# Bottom.net
KiCad netlist of a schematic drawn in EAGLE
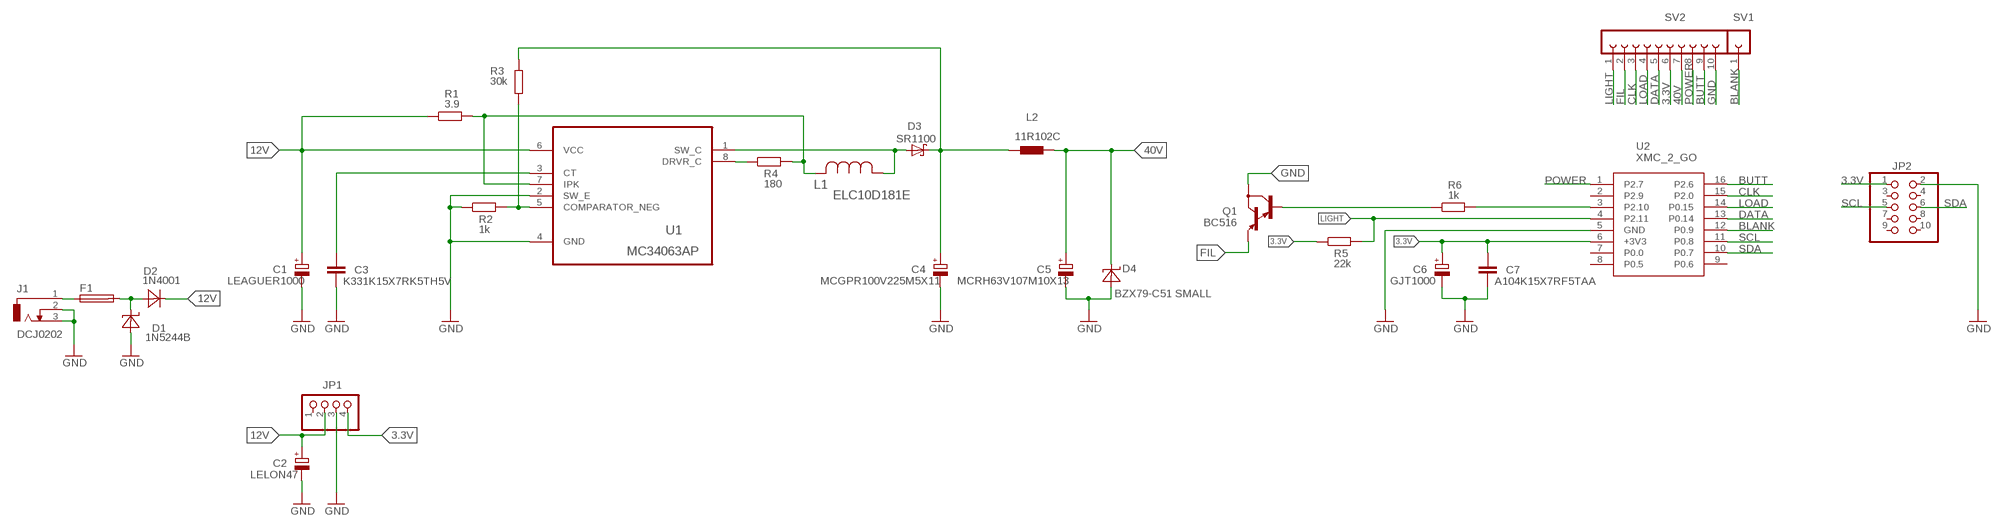
[diagram p0: schematic, sheet 1]

(export (version "E")
  (design (tool "Eeschema 10.0.6"))
  (components
    (comp (ref "C1")
      (value "LEAGUER1000")
      (footprint "eagle-import:E5-10")
      (libsource (lib "eagle-import") (part "LEAGUER1000"))
    )
    (comp (ref "C2")
      (value "LELON47")
      (footprint "eagle-import:E2,5-6")
      (libsource (lib "eagle-import") (part "LELON47"))
    )
    (comp (ref "C3")
      (value "K331K15X7RK5TH5V")
      (footprint "eagle-import:C025-025X050")
      (libsource (lib "eagle-import") (part "K331K15X7RK5TH5V"))
    )
    (comp (ref "C4")
      (value "MCGPR100V225M5X11")
      (footprint "eagle-import:E2,5-5")
      (libsource (lib "eagle-import") (part "MCGPR100V225M5X11"))
    )
    (comp (ref "C5")
      (value "MCRH63V107M10X13")
      (footprint "eagle-import:E5-10")
      (libsource (lib "eagle-import") (part "MCRH63V107M10X13"))
    )
    (comp (ref "C6")
      (value "GJT1000")
      (footprint "eagle-import:E2,5-8")
      (libsource (lib "eagle-import") (part "GJT1000"))
    )
    (comp (ref "C7")
      (value "A104K15X7RF5TAA")
      (footprint "eagle-import:C025-025X050")
      (libsource (lib "eagle-import") (part "A104K15X7RF5TAA"))
    )
    (comp (ref "D1")
      (value "1N5244B")
      (footprint "eagle-import:DO41-7")
      (libsource (lib "eagle-import") (part "1N5244B"))
    )
    (comp (ref "D2")
      (value "1N4001")
      (footprint "eagle-import:DO41-7")
      (libsource (lib "eagle-import") (part "1N4001"))
    )
    (comp (ref "D3")
      (value "SR1100")
      (footprint "eagle-import:DO41-7")
      (libsource (lib "eagle-import") (part "SR1100"))
    )
    (comp (ref "D4")
      (value "BZX79-C51 SMALL")
      (footprint "eagle-import:DO35-7")
      (libsource (lib "eagle-import") (part "BZX79-C51"))
    )
    (comp (ref "F1")
      (value "SH22,5")
      (footprint "eagle-import:SH22,5")
      (fields (field (name "MF") "SCHURTER") (field (name "MPN") "0031.8201"))
      (libsource (lib "eagle-import") (part "SH22,5"))
    )
    (comp (ref "J1")
      (value "DCJ0202")
      (footprint "eagle-import:DCJ0202")
      (libsource (lib "eagle-import") (part "DCJ0202"))
    )
    (comp (ref "JP1")
      (value "PINHD-1X4")
      (footprint "eagle-import:1X04")
      (libsource (lib "eagle-import") (part "PINHD-1X4"))
    )
    (comp (ref "JP2")
      (value "PINHD-2X5/90")
      (footprint "eagle-import:2X05_90")
      (libsource (lib "eagle-import") (part "PINHD-2X5/90"))
    )
    (comp (ref "L1")
      (value "ELC10D181E")
      (footprint "eagle-import:IND_ELC10D")
      (libsource (lib "eagle-import") (part "ELC-10D10D181E"))
    )
    (comp (ref "L2")
      (value "11R102C")
      (footprint "eagle-import:L2,5-5")
      (libsource (lib "eagle-import") (part "11R102C"))
    )
    (comp (ref "Q1")
      (value "BC516")
      (footprint "eagle-import:TO92")
      (libsource (lib "eagle-import") (part "BC516"))
    )
    (comp (ref "R1")
      (value "3.9")
      (footprint "eagle-import:0207_10")
      (libsource (lib "eagle-import") (part "R-EU_0207/10"))
    )
    (comp (ref "R2")
      (value "1k")
      (footprint "eagle-import:0207_10")
      (libsource (lib "eagle-import") (part "R-EU_0207/10"))
    )
    (comp (ref "R3")
      (value "30k")
      (footprint "eagle-import:0207_10")
      (libsource (lib "eagle-import") (part "R-EU_0207/10"))
    )
    (comp (ref "R4")
      (value "180")
      (footprint "eagle-import:0207_10")
      (libsource (lib "eagle-import") (part "R-EU_0207/10"))
    )
    (comp (ref "R5")
      (value "22k")
      (footprint "eagle-import:0207_10")
      (libsource (lib "eagle-import") (part "R-EU_0207/10"))
    )
    (comp (ref "R6")
      (value "1k")
      (footprint "eagle-import:0207_10")
      (libsource (lib "eagle-import") (part "R-EU_0207/10"))
    )
    (comp (ref "SV1")
      (value "FE01")
      (footprint "eagle-import:FE05-1")
      (libsource (lib "eagle-import") (part "FE01"))
    )
    (comp (ref "SV2")
      (value "FE10-1")
      (footprint "eagle-import:FE10")
      (libsource (lib "eagle-import") (part "FE10-1"))
    )
    (comp (ref "U1")
      (value "MC34063AP")
      (footprint "eagle-import:DIP254P762X508-8")
      (libsource (lib "eagle-import") (part "MC34063AP"))
    )
    (comp (ref "U2")
      (value "XMC_2_GO")
      (footprint "eagle-import:XMC_2_GO")
      (libsource (lib "eagle-import") (part "XMC_2_GO"))
    )
  )
  (nets
    (net (code "1") (name "/BLANK") (class "Default")
      (node (ref "SV1") (pin "1") (pinfunction "5_1") (pintype "passive"))
      (node (ref "U2") (pin "12") (pinfunction "P0.9_12") (pintype "bidirectional"))
    )
    (net (code "2") (name "/BUTT") (class "Default")
      (node (ref "SV2") (pin "9") (pinfunction "9_9") (pintype "passive"))
      (node (ref "U2") (pin "16") (pinfunction "P2.6_16") (pintype "bidirectional"))
    )
    (net (code "3") (name "/CLK") (class "Default")
      (node (ref "SV2") (pin "3") (pinfunction "3_3") (pintype "passive"))
      (node (ref "U2") (pin "15") (pinfunction "P2.0_15") (pintype "bidirectional"))
    )
    (net (code "4") (name "/DATA") (class "Default")
      (node (ref "SV2") (pin "5") (pinfunction "5_5") (pintype "passive"))
      (node (ref "U2") (pin "13") (pinfunction "P0.14_13") (pintype "bidirectional"))
    )
    (net (code "5") (name "/LOAD") (class "Default")
      (node (ref "SV2") (pin "4") (pinfunction "4_4") (pintype "passive"))
      (node (ref "U2") (pin "14") (pinfunction "P0.15_14") (pintype "bidirectional"))
    )
    (net (code "6") (name "/POWER") (class "Default")
      (node (ref "SV2") (pin "8") (pinfunction "8_8") (pintype "passive"))
      (node (ref "U2") (pin "1") (pinfunction "P2.7_1") (pintype "bidirectional"))
    )
    (net (code "7") (name "/SCL") (class "Default")
      (node (ref "JP2") (pin "5") (pinfunction "5_5") (pintype "passive"))
      (node (ref "U2") (pin "11") (pinfunction "P0.8_11") (pintype "bidirectional"))
    )
    (net (code "8") (name "/SDA") (class "Default")
      (node (ref "JP2") (pin "6") (pinfunction "6_6") (pintype "passive"))
      (node (ref "U2") (pin "10") (pinfunction "P0.7_10") (pintype "bidirectional"))
    )
    (net (code "9") (name "3.3V") (class "Default")
      (node (ref "C6") (pin "+") (pinfunction "+_+") (pintype "passive"))
      (node (ref "C7") (pin "1") (pinfunction "1_1") (pintype "passive"))
      (node (ref "JP1") (pin "4") (pinfunction "4_4") (pintype "passive"))
      (node (ref "JP2") (pin "1") (pinfunction "1_1") (pintype "passive"))
      (node (ref "R5") (pin "1") (pinfunction "1_1") (pintype "passive"))
      (node (ref "SV2") (pin "6") (pinfunction "6_6") (pintype "passive"))
      (node (ref "U2") (pin "6") (pinfunction "+3V3_6") (pintype "bidirectional"))
    )
    (net (code "10") (name "12V") (class "Default")
      (node (ref "C1") (pin "+") (pinfunction "+_+") (pintype "passive"))
      (node (ref "C2") (pin "+") (pinfunction "+_+") (pintype "passive"))
      (node (ref "D2") (pin "C") (pinfunction "C_C") (pintype "passive"))
      (node (ref "JP1") (pin "2") (pinfunction "2_2") (pintype "passive"))
      (node (ref "R1") (pin "1") (pinfunction "1_1") (pintype "passive"))
      (node (ref "U1") (pin "6") (pinfunction "VCC_6") (pintype "power_in"))
    )
    (net (code "11") (name "40V") (class "Default")
      (node (ref "C5") (pin "+") (pinfunction "+_+") (pintype "passive"))
      (node (ref "D4") (pin "C") (pinfunction "C_C") (pintype "passive"))
      (node (ref "L2") (pin "2") (pinfunction "2_2") (pintype "passive"))
      (node (ref "SV2") (pin "7") (pinfunction "7_7") (pintype "passive"))
    )
    (net (code "12") (name "FIL") (class "Default")
      (node (ref "Q1") (pin "1") (pinfunction "E_1") (pintype "passive"))
      (node (ref "SV2") (pin "2") (pinfunction "2_2") (pintype "passive"))
    )
    (net (code "13") (name "GND") (class "Default")
      (node (ref "C1") (pin "-") (pinfunction "-_-") (pintype "passive"))
      (node (ref "C2") (pin "-") (pinfunction "-_-") (pintype "passive"))
      (node (ref "C3") (pin "2") (pinfunction "2_2") (pintype "passive"))
      (node (ref "C4") (pin "-") (pinfunction "-_-") (pintype "passive"))
      (node (ref "C5") (pin "-") (pinfunction "-_-") (pintype "passive"))
      (node (ref "C6") (pin "-") (pinfunction "-_-") (pintype "passive"))
      (node (ref "C7") (pin "2") (pinfunction "2_2") (pintype "passive"))
      (node (ref "D1") (pin "A") (pinfunction "A_A") (pintype "passive"))
      (node (ref "D4") (pin "A") (pinfunction "A_A") (pintype "passive"))
      (node (ref "J1") (pin "2") (pinfunction "2_2") (pintype "passive"))
      (node (ref "J1") (pin "3") (pinfunction "3_3") (pintype "passive"))
      (node (ref "JP1") (pin "3") (pinfunction "3_3") (pintype "passive"))
      (node (ref "JP2") (pin "2") (pinfunction "2_2") (pintype "passive"))
      (node (ref "Q1") (pin "3") (pinfunction "C_3") (pintype "passive"))
      (node (ref "R2") (pin "1") (pinfunction "1_1") (pintype "passive"))
      (node (ref "SV2") (pin "10") (pinfunction "10_10") (pintype "passive"))
      (node (ref "U1") (pin "2") (pinfunction "SW_E_2") (pintype "input"))
      (node (ref "U1") (pin "4") (pinfunction "GND_4") (pintype "passive"))
      (node (ref "U2") (pin "5") (pinfunction "GND_5") (pintype "bidirectional"))
    )
    (net (code "14") (name "LIGHT") (class "Default")
      (node (ref "R5") (pin "2") (pinfunction "2_2") (pintype "passive"))
      (node (ref "SV2") (pin "1") (pinfunction "1_1") (pintype "passive"))
      (node (ref "U2") (pin "4") (pinfunction "P2.11_4") (pintype "bidirectional"))
    )
    (net (code "15") (name "Net-(C4-Pad+)") (class "Default")
      (node (ref "C4") (pin "+") (pinfunction "+_+") (pintype "passive"))
      (node (ref "D3") (pin "C") (pinfunction "C_C") (pintype "passive"))
      (node (ref "L2") (pin "1") (pinfunction "1_1") (pintype "passive"))
      (node (ref "R3") (pin "1") (pinfunction "1_1") (pintype "passive"))
    )
    (net (code "16") (name "Net-(D1-PadC)") (class "Default")
      (node (ref "D1") (pin "C") (pinfunction "C_C") (pintype "passive"))
      (node (ref "D2") (pin "A") (pinfunction "A_A") (pintype "passive"))
      (node (ref "F1") (pin "2") (pinfunction "2_2") (pintype "passive"))
    )
    (net (code "17") (name "Net-(F1-Pad1)") (class "Default")
      (node (ref "F1") (pin "1") (pinfunction "1_1") (pintype "passive"))
      (node (ref "J1") (pin "1") (pinfunction "1_1") (pintype "passive"))
    )
    (net (code "18") (name "Net-(Q1-B)") (class "Default")
      (node (ref "Q1") (pin "2") (pinfunction "B_2") (pintype "passive"))
      (node (ref "R6") (pin "1") (pinfunction "1_1") (pintype "passive"))
    )
    (net (code "19") (name "Net-(U1-COMPARATOR_NEG)") (class "Default")
      (node (ref "R2") (pin "2") (pinfunction "2_2") (pintype "passive"))
      (node (ref "R3") (pin "2") (pinfunction "2_2") (pintype "passive"))
      (node (ref "U1") (pin "5") (pinfunction "COMPARATOR_NEG_5") (pintype "input"))
    )
    (net (code "20") (name "Net-(U1-CT)") (class "Default")
      (node (ref "C3") (pin "1") (pinfunction "1_1") (pintype "passive"))
      (node (ref "U1") (pin "3") (pinfunction "CT_3") (pintype "input"))
    )
    (net (code "21") (name "Net-(U1-DRVR_C)") (class "Default")
      (node (ref "R4") (pin "1") (pinfunction "1_1") (pintype "passive"))
      (node (ref "U1") (pin "8") (pinfunction "DRVR_C_8") (pintype "passive"))
    )
    (net (code "22") (name "Net-(U1-IPK)") (class "Default")
      (node (ref "L1") (pin "2") (pinfunction "2_2") (pintype "passive"))
      (node (ref "R1") (pin "2") (pinfunction "2_2") (pintype "passive"))
      (node (ref "R4") (pin "2") (pinfunction "2_2") (pintype "passive"))
      (node (ref "U1") (pin "7") (pinfunction "IPK_7") (pintype "input"))
    )
    (net (code "23") (name "Net-(U1-SW_C)") (class "Default")
      (node (ref "D3") (pin "A") (pinfunction "A_A") (pintype "passive"))
      (node (ref "L1") (pin "1") (pinfunction "1_1") (pintype "passive"))
      (node (ref "U1") (pin "1") (pinfunction "SW_C_1") (pintype "passive"))
    )
    (net (code "24") (name "Net-(U2-P2.10)") (class "Default")
      (node (ref "R6") (pin "2") (pinfunction "2_2") (pintype "passive"))
      (node (ref "U2") (pin "3") (pinfunction "P2.10_3") (pintype "bidirectional"))
    )
    (net (code "25") (name "unconnected-(JP1-Pad1)") (class "Default")
      (node (ref "JP1") (pin "1") (pinfunction "1_1") (pintype "passive"))
    )
    (net (code "26") (name "unconnected-(JP2-Pad3)") (class "Default")
      (node (ref "JP2") (pin "3") (pinfunction "3_3") (pintype "passive"))
    )
    (net (code "27") (name "unconnected-(JP2-Pad4)") (class "Default")
      (node (ref "JP2") (pin "4") (pinfunction "4_4") (pintype "passive"))
    )
    (net (code "28") (name "unconnected-(JP2-Pad7)") (class "Default")
      (node (ref "JP2") (pin "7") (pinfunction "7_7") (pintype "passive"))
    )
    (net (code "29") (name "unconnected-(JP2-Pad8)") (class "Default")
      (node (ref "JP2") (pin "8") (pinfunction "8_8") (pintype "passive"))
    )
    (net (code "30") (name "unconnected-(JP2-Pad9)") (class "Default")
      (node (ref "JP2") (pin "9") (pinfunction "9_9") (pintype "passive"))
    )
    (net (code "31") (name "unconnected-(JP2-Pad10)") (class "Default")
      (node (ref "JP2") (pin "10") (pinfunction "10_10") (pintype "passive"))
    )
    (net (code "32") (name "unconnected-(U2-P0.0-Pad7)") (class "Default")
      (node (ref "U2") (pin "7") (pinfunction "P0.0_7") (pintype "bidirectional"))
    )
    (net (code "33") (name "unconnected-(U2-P0.5-Pad8)") (class "Default")
      (node (ref "U2") (pin "8") (pinfunction "P0.5_8") (pintype "bidirectional"))
    )
    (net (code "34") (name "unconnected-(U2-P0.6-Pad9)") (class "Default")
      (node (ref "U2") (pin "9") (pinfunction "P0.6_9") (pintype "bidirectional"))
    )
    (net (code "35") (name "unconnected-(U2-P2.9-Pad2)") (class "Default")
      (node (ref "U2") (pin "2") (pinfunction "P2.9_2") (pintype "bidirectional"))
    )
  )
)
